# Top.net
KiCad netlist of a schematic drawn in Altium Designer
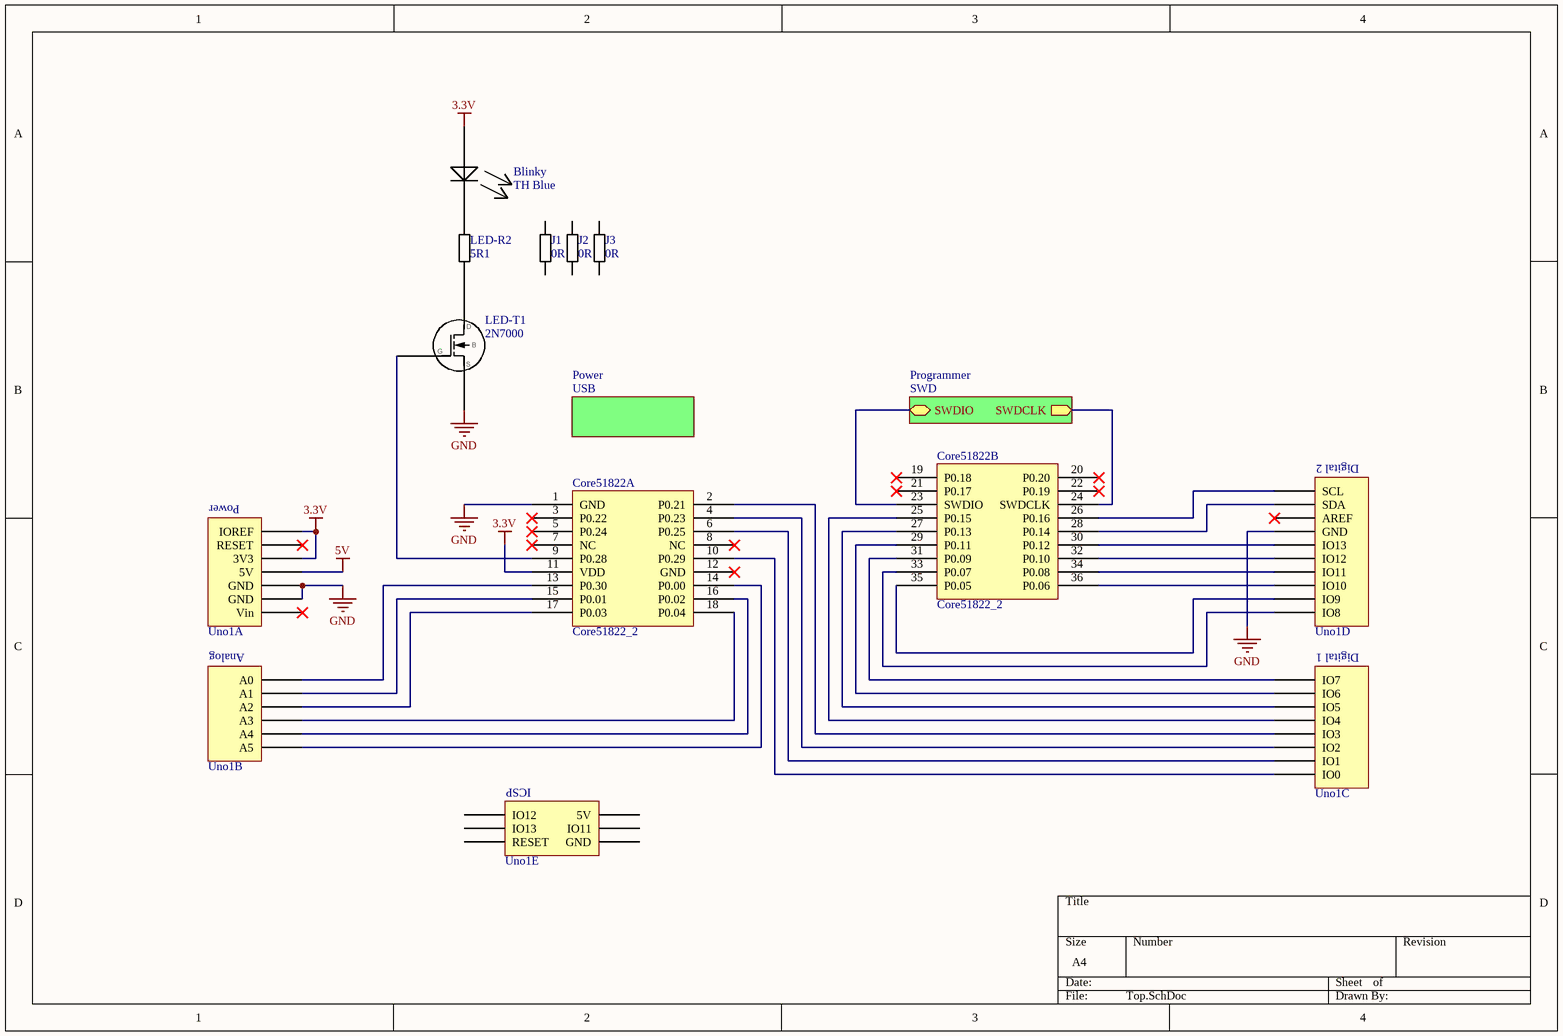
[diagram p0: Top.SchDoc]

(export (version "E")
  (design (tool "Eeschema 10.0.6"))
  (components
    (comp (ref "Blinky") (value "TH Blue") (footprint "LED 3mm") (libsource (lib "LEDs") (part "LED")))
    (comp (ref "Core51822")
      (value "Core51822_2")
      (footprint "Core51822")
      (libsource (lib "Modules") (part "Core51822_2"))
    )
    (comp (ref "J1")
      (value "0R")
      (footprint "R 0805 / 2012 wide")
      (libsource (lib "Standard") (part "Resistor"))
    )
    (comp (ref "J2")
      (value "0R")
      (footprint "R 0805 / 2012 wide")
      (libsource (lib "Standard") (part "Resistor"))
    )
    (comp (ref "J3")
      (value "0R")
      (footprint "R 0805 / 2012 wide")
      (libsource (lib "Standard") (part "Resistor"))
    )
    (comp (ref "LED-R2")
      (value "5R1")
      (footprint "R 0805 / 2012 wide")
      (libsource (lib "Standard") (part "Resistor"))
    )
    (comp (ref "LED-T1")
      (value "2N7000")
      (footprint "SOT-23-3")
      (description "N-FET")
      (libsource (lib "ICs") (part "2N7000"))
    )
    (comp (ref "Uno1")
      (value "Arduino Uno")
      (footprint "Arduino Uno Adapter")
      (libsource (lib "Arduino") (part "Arduino Uno"))
    )
  )
  (nets
    (net (code "1") (name "/SWDCLK") (class "Default")
      (node (ref "Core51822") (pin "24") (pinfunction "SWDCLK_24") (pintype "passive"))
    )
    (net (code "2") (name "/SWDIO") (class "Default")
      (node (ref "Core51822") (pin "23") (pinfunction "SWDIO_23") (pintype "passive"))
    )
    (net (code "3") (name "3.3V") (class "Default")
      (node (ref "Blinky") (pin "1") (pinfunction "+_1") (pintype "passive"))
      (node (ref "Core51822") (pin "11") (pinfunction "VDD_11") (pintype "passive"))
      (node (ref "Uno1") (pin "3V3") (pinfunction "3V3_3V3") (pintype "passive"))
      (node (ref "Uno1") (pin "IOREF") (pinfunction "IOREF_IOREF") (pintype "passive"))
    )
    (net (code "4") (name "5V") (class "Default")
      (node (ref "Uno1") (pin "5V") (pinfunction "5V_5V") (pintype "passive"))
    )
    (net (code "5") (name "GND") (class "Default")
      (node (ref "Core51822") (pin "1") (pinfunction "GND_1") (pintype "passive"))
      (node (ref "LED-T1") (pin "2") (pinfunction "2_2") (pintype "passive"))
      (node (ref "Uno1") (pin "GND1") (pinfunction "GND_GND1") (pintype "passive"))
      (node (ref "Uno1") (pin "GND2") (pinfunction "GND_GND2") (pintype "passive"))
      (node (ref "Uno1") (pin "GND3") (pinfunction "GND_GND3") (pintype "passive"))
    )
    (net (code "6") (name "Net-(Blinky--)") (class "Default")
      (node (ref "Blinky") (pin "2") (pinfunction "-_2") (pintype "passive"))
      (node (ref "LED-R2") (pin "2") (pinfunction "2_2") (pintype "passive"))
    )
    (net (code "7") (name "Net-(Core51822A-P0.00)") (class "Default")
      (node (ref "Core51822") (pin "14") (pinfunction "P0.00_14") (pintype "passive"))
      (node (ref "Uno1") (pin "A5") (pinfunction "A5_A5") (pintype "passive"))
    )
    (net (code "8") (name "Net-(Core51822A-P0.01)") (class "Default")
      (node (ref "Core51822") (pin "15") (pinfunction "P0.01_15") (pintype "passive"))
      (node (ref "Uno1") (pin "A1") (pinfunction "A1_A1") (pintype "passive"))
    )
    (net (code "9") (name "Net-(Core51822A-P0.02)") (class "Default")
      (node (ref "Core51822") (pin "16") (pinfunction "P0.02_16") (pintype "passive"))
      (node (ref "Uno1") (pin "A4") (pinfunction "A4_A4") (pintype "passive"))
    )
    (net (code "10") (name "Net-(Core51822A-P0.03)") (class "Default")
      (node (ref "Core51822") (pin "17") (pinfunction "P0.03_17") (pintype "passive"))
      (node (ref "Uno1") (pin "A2") (pinfunction "A2_A2") (pintype "passive"))
    )
    (net (code "11") (name "Net-(Core51822A-P0.04)") (class "Default")
      (node (ref "Core51822") (pin "18") (pinfunction "P0.04_18") (pintype "passive"))
      (node (ref "Uno1") (pin "A3") (pinfunction "A3_A3") (pintype "passive"))
    )
    (net (code "12") (name "Net-(Core51822A-P0.21)") (class "Default")
      (node (ref "Core51822") (pin "2") (pinfunction "P0.21_2") (pintype "passive"))
      (node (ref "Uno1") (pin "3") (pinfunction "IO3_3") (pintype "passive"))
    )
    (net (code "13") (name "Net-(Core51822A-P0.23)") (class "Default")
      (node (ref "Core51822") (pin "4") (pinfunction "P0.23_4") (pintype "passive"))
      (node (ref "Uno1") (pin "2") (pinfunction "IO2_2") (pintype "passive"))
    )
    (net (code "14") (name "Net-(Core51822A-P0.25)") (class "Default")
      (node (ref "Core51822") (pin "6") (pinfunction "P0.25_6") (pintype "passive"))
      (node (ref "Uno1") (pin "1") (pinfunction "IO1_1") (pintype "passive"))
    )
    (net (code "15") (name "Net-(Core51822A-P0.28)") (class "Default")
      (node (ref "Core51822") (pin "9") (pinfunction "P0.28_9") (pintype "passive"))
      (node (ref "LED-T1") (pin "1") (pinfunction "1_1") (pintype "passive"))
    )
    (net (code "16") (name "Net-(Core51822A-P0.29)") (class "Default")
      (node (ref "Core51822") (pin "10") (pinfunction "P0.29_10") (pintype "passive"))
      (node (ref "Uno1") (pin "0") (pinfunction "IO0_0") (pintype "passive"))
    )
    (net (code "17") (name "Net-(Core51822A-P0.30)") (class "Default")
      (node (ref "Core51822") (pin "13") (pinfunction "P0.30_13") (pintype "passive"))
      (node (ref "Uno1") (pin "A0") (pinfunction "A0_A0") (pintype "passive"))
    )
    (net (code "18") (name "Net-(Core51822B-P0.05)") (class "Default")
      (node (ref "Core51822") (pin "35") (pinfunction "P0.05_35") (pintype "passive"))
      (node (ref "Uno1") (pin "9") (pinfunction "IO9_9") (pintype "passive"))
    )
    (net (code "19") (name "Net-(Core51822B-P0.06)") (class "Default")
      (node (ref "Core51822") (pin "36") (pinfunction "P0.06_36") (pintype "passive"))
      (node (ref "Uno1") (pin "10") (pinfunction "IO10_10") (pintype "passive"))
    )
    (net (code "20") (name "Net-(Core51822B-P0.07)") (class "Default")
      (node (ref "Core51822") (pin "33") (pinfunction "P0.07_33") (pintype "passive"))
      (node (ref "Uno1") (pin "8") (pinfunction "IO8_8") (pintype "passive"))
    )
    (net (code "21") (name "Net-(Core51822B-P0.08)") (class "Default")
      (node (ref "Core51822") (pin "34") (pinfunction "P0.08_34") (pintype "passive"))
      (node (ref "Uno1") (pin "11") (pinfunction "IO11_11") (pintype "passive"))
    )
    (net (code "22") (name "Net-(Core51822B-P0.09)") (class "Default")
      (node (ref "Core51822") (pin "31") (pinfunction "P0.09_31") (pintype "passive"))
      (node (ref "Uno1") (pin "7") (pinfunction "IO7_7") (pintype "passive"))
    )
    (net (code "23") (name "Net-(Core51822B-P0.10)") (class "Default")
      (node (ref "Core51822") (pin "32") (pinfunction "P0.10_32") (pintype "passive"))
      (node (ref "Uno1") (pin "12") (pinfunction "IO12_12") (pintype "passive"))
    )
    (net (code "24") (name "Net-(Core51822B-P0.11)") (class "Default")
      (node (ref "Core51822") (pin "29") (pinfunction "P0.11_29") (pintype "passive"))
      (node (ref "Uno1") (pin "6") (pinfunction "IO6_6") (pintype "passive"))
    )
    (net (code "25") (name "Net-(Core51822B-P0.12)") (class "Default")
      (node (ref "Core51822") (pin "30") (pinfunction "P0.12_30") (pintype "passive"))
      (node (ref "Uno1") (pin "13") (pinfunction "IO13_13") (pintype "passive"))
    )
    (net (code "26") (name "Net-(Core51822B-P0.13)") (class "Default")
      (node (ref "Core51822") (pin "27") (pinfunction "P0.13_27") (pintype "passive"))
      (node (ref "Uno1") (pin "5") (pinfunction "IO5_5") (pintype "passive"))
    )
    (net (code "27") (name "Net-(Core51822B-P0.14)") (class "Default")
      (node (ref "Core51822") (pin "28") (pinfunction "P0.14_28") (pintype "passive"))
      (node (ref "Uno1") (pin "SDA") (pinfunction "SDA_SDA") (pintype "passive"))
    )
    (net (code "28") (name "Net-(Core51822B-P0.15)") (class "Default")
      (node (ref "Core51822") (pin "25") (pinfunction "P0.15_25") (pintype "passive"))
      (node (ref "Uno1") (pin "4") (pinfunction "IO4_4") (pintype "passive"))
    )
    (net (code "29") (name "Net-(Core51822B-P0.16)") (class "Default")
      (node (ref "Core51822") (pin "26") (pinfunction "P0.16_26") (pintype "passive"))
      (node (ref "Uno1") (pin "SCL") (pinfunction "SCL_SCL") (pintype "passive"))
    )
    (net (code "30") (name "Net-(LED-R2-Pad1)") (class "Default")
      (node (ref "LED-R2") (pin "1") (pinfunction "1_1") (pintype "passive"))
      (node (ref "LED-T1") (pin "3") (pinfunction "3_3") (pintype "passive"))
    )
    (net (code "31") (name "unconnected-(Core51822A-GND-Pad12)") (class "Default")
      (node (ref "Core51822") (pin "12") (pinfunction "GND_12") (pintype "passive+no_connect"))
    )
    (net (code "32") (name "unconnected-(Core51822A-NC-Pad7)") (class "Default")
      (node (ref "Core51822") (pin "7") (pinfunction "NC_7") (pintype "passive+no_connect"))
    )
    (net (code "33") (name "unconnected-(Core51822A-NC-Pad8)") (class "Default")
      (node (ref "Core51822") (pin "8") (pinfunction "NC_8") (pintype "passive+no_connect"))
    )
    (net (code "34") (name "unconnected-(Core51822A-P0.22-Pad3)") (class "Default")
      (node (ref "Core51822") (pin "3") (pinfunction "P0.22_3") (pintype "passive+no_connect"))
    )
    (net (code "35") (name "unconnected-(Core51822A-P0.24-Pad5)") (class "Default")
      (node (ref "Core51822") (pin "5") (pinfunction "P0.24_5") (pintype "passive+no_connect"))
    )
    (net (code "36") (name "unconnected-(Core51822B-P0.17-Pad21)") (class "Default")
      (node (ref "Core51822") (pin "21") (pinfunction "P0.17_21") (pintype "power_in+no_connect"))
    )
    (net (code "37") (name "unconnected-(Core51822B-P0.18-Pad19)") (class "Default")
      (node (ref "Core51822") (pin "19") (pinfunction "P0.18_19") (pintype "passive+no_connect"))
    )
    (net (code "38") (name "unconnected-(Core51822B-P0.19-Pad22)") (class "Default")
      (node (ref "Core51822") (pin "22") (pinfunction "P0.19_22") (pintype "passive+no_connect"))
    )
    (net (code "39") (name "unconnected-(Core51822B-P0.20-Pad20)") (class "Default")
      (node (ref "Core51822") (pin "20") (pinfunction "P0.20_20") (pintype "passive+no_connect"))
    )
    (net (code "40") (name "unconnected-(J1-Pad1)") (class "Default")
      (node (ref "J1") (pin "1") (pinfunction "1_1") (pintype "passive"))
    )
    (net (code "41") (name "unconnected-(J1-Pad2)") (class "Default")
      (node (ref "J1") (pin "2") (pinfunction "2_2") (pintype "passive"))
    )
    (net (code "42") (name "unconnected-(J2-Pad1)") (class "Default")
      (node (ref "J2") (pin "1") (pinfunction "1_1") (pintype "passive"))
    )
    (net (code "43") (name "unconnected-(J2-Pad2)") (class "Default")
      (node (ref "J2") (pin "2") (pinfunction "2_2") (pintype "passive"))
    )
    (net (code "44") (name "unconnected-(J3-Pad1)") (class "Default")
      (node (ref "J3") (pin "1") (pinfunction "1_1") (pintype "passive"))
    )
    (net (code "45") (name "unconnected-(J3-Pad2)") (class "Default")
      (node (ref "J3") (pin "2") (pinfunction "2_2") (pintype "passive"))
    )
    (net (code "46") (name "unconnected-(Uno1-PadAREF)") (class "Default")
      (node (ref "Uno1") (pin "AREF") (pinfunction "AREF_AREF") (pintype "passive+no_connect"))
    )
    (net (code "47") (name "unconnected-(Uno1-PadRESET)") (class "Default")
      (node (ref "Uno1") (pin "RESET") (pinfunction "RESET_RESET") (pintype "passive+no_connect"))
    )
    (net (code "48") (name "unconnected-(Uno1-PadVin)") (class "Default")
      (node (ref "Uno1") (pin "Vin") (pinfunction "Vin_Vin") (pintype "passive+no_connect"))
    )
    (net (code "49") (name "unconnected-(Uno1E-5V-PadICSP2)") (class "Default")
      (node (ref "Uno1") (pin "ICSP2") (pinfunction "5V_ICSP2") (pintype "passive"))
    )
    (net (code "50") (name "unconnected-(Uno1E-GND-PadICSP6)") (class "Default")
      (node (ref "Uno1") (pin "ICSP6") (pinfunction "GND_ICSP6") (pintype "passive"))
    )
    (net (code "51") (name "unconnected-(Uno1E-IO11-PadICSP4)") (class "Default")
      (node (ref "Uno1") (pin "ICSP4") (pinfunction "IO11_ICSP4") (pintype "passive"))
    )
    (net (code "52") (name "unconnected-(Uno1E-IO12-PadICSP1)") (class "Default")
      (node (ref "Uno1") (pin "ICSP1") (pinfunction "IO12_ICSP1") (pintype "passive"))
    )
    (net (code "53") (name "unconnected-(Uno1E-IO13-PadICSP3)") (class "Default")
      (node (ref "Uno1") (pin "ICSP3") (pinfunction "IO13_ICSP3") (pintype "passive"))
    )
    (net (code "54") (name "unconnected-(Uno1E-RESET-PadICSP5)") (class "Default")
      (node (ref "Uno1") (pin "ICSP5") (pinfunction "RESET_ICSP5") (pintype "passive"))
    )
  )
)
